# HD3SS460-PORT_1.net
KiCad netlist of a schematic drawn in Altium Designer
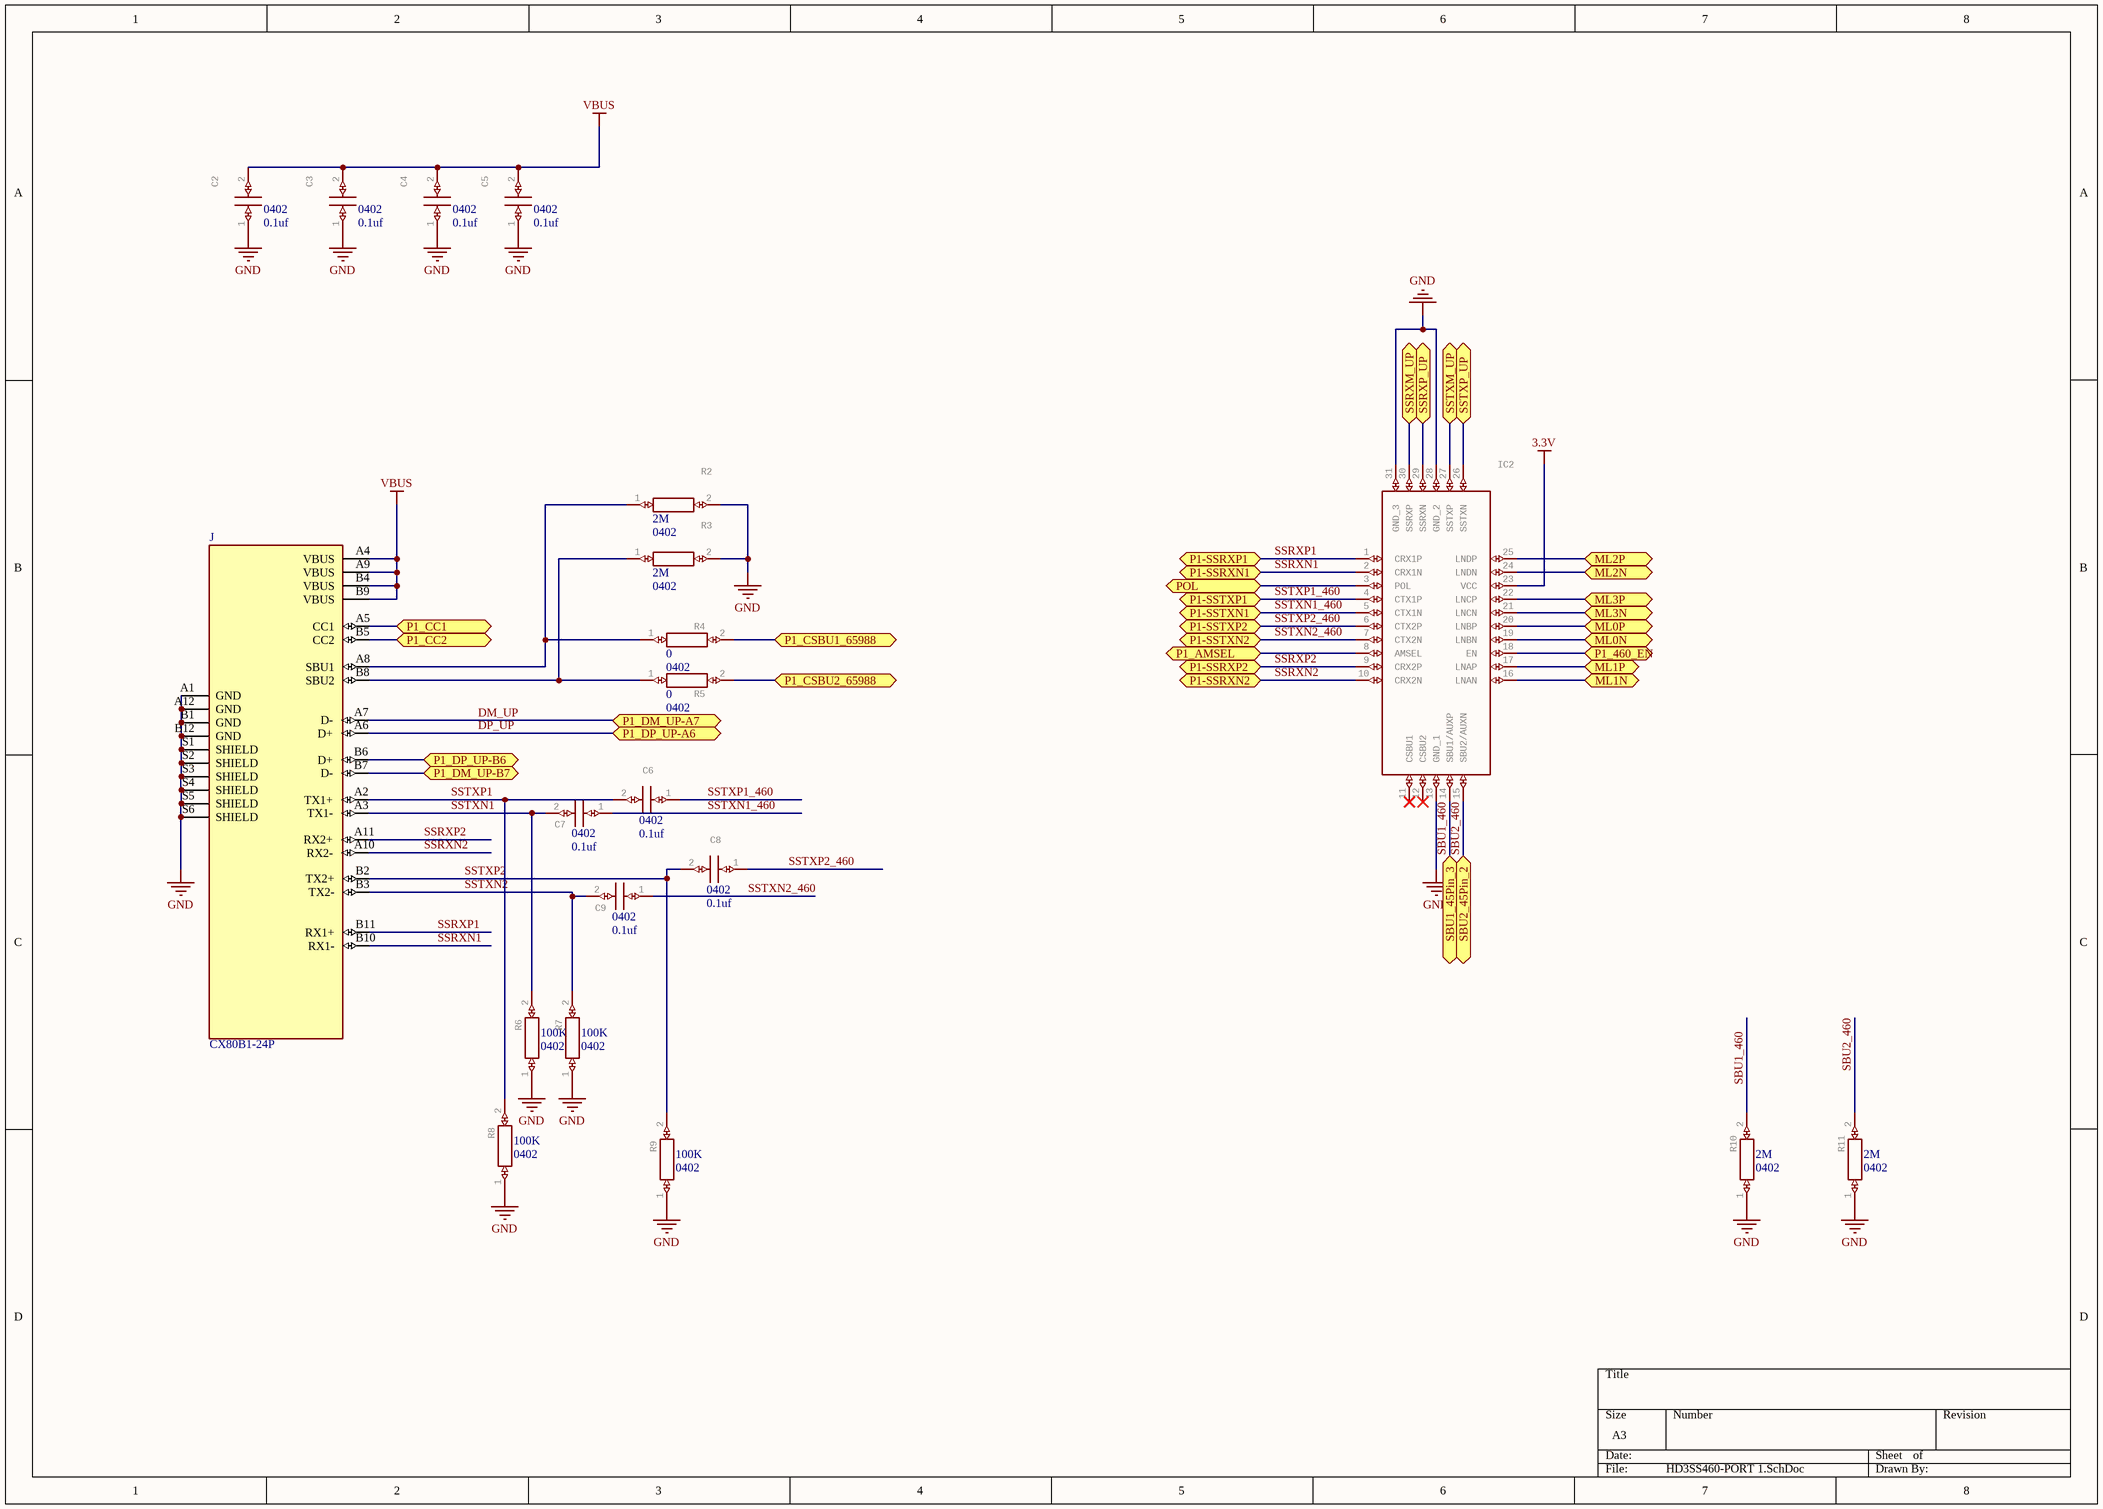
[diagram p0: HD3SS460-PORT 1.SchDoc]

(export (version "E")
  (design (tool "Eeschema 10.0.6"))
  (components
    (comp (ref "C2")
      (value "0.1uf")
      (footprint "CAPC1005X56N")
      (fields
        (field (name "MANUFACTURER_PART_NUMBER") "04025C104KAT2A")
        (field (name "MOUSER_PART_NUMBER") "581-04025C104KAT2A")
        (field (name "PACKAGE") "0402")
        (field (name "Comment") "Multilayer Ceramic Capacitors MLCC - SMD/SMT 50V .1uF X7R 0402 10% Tol   Source:  Datasheet")
      )
      (libsource (lib "C0402-GP") (part "04025C104KAT2A"))
    )
    (comp (ref "C3")
      (value "0.1uf")
      (footprint "CAPC1005X56N")
      (fields
        (field (name "MANUFACTURER_PART_NUMBER") "04025C104KAT2A")
        (field (name "MOUSER_PART_NUMBER") "581-04025C104KAT2A")
        (field (name "PACKAGE") "0402")
        (field (name "Comment") "Multilayer Ceramic Capacitors MLCC - SMD/SMT 50V .1uF X7R 0402 10% Tol   Source:  Datasheet")
      )
      (libsource (lib "C0402-GP") (part "04025C104KAT2A"))
    )
    (comp (ref "C4")
      (value "0.1uf")
      (footprint "CAPC1005X56N")
      (fields
        (field (name "MANUFACTURER_PART_NUMBER") "04025C104KAT2A")
        (field (name "MOUSER_PART_NUMBER") "581-04025C104KAT2A")
        (field (name "PACKAGE") "0402")
        (field (name "Comment") "Multilayer Ceramic Capacitors MLCC - SMD/SMT 50V .1uF X7R 0402 10% Tol   Source:  Datasheet")
      )
      (libsource (lib "C0402-GP") (part "04025C104KAT2A"))
    )
    (comp (ref "C5")
      (value "0.1uf")
      (footprint "CAPC1005X56N")
      (fields
        (field (name "MANUFACTURER_PART_NUMBER") "04025C104KAT2A")
        (field (name "MOUSER_PART_NUMBER") "581-04025C104KAT2A")
        (field (name "PACKAGE") "0402")
        (field (name "Comment") "Multilayer Ceramic Capacitors MLCC - SMD/SMT 50V .1uF X7R 0402 10% Tol   Source:  Datasheet")
      )
      (libsource (lib "C0402-GP") (part "04025C104KAT2A"))
    )
    (comp (ref "C6")
      (value "0.1uf")
      (footprint "CAPC1005X56N")
      (fields
        (field (name "MANUFACTURER_PART_NUMBER") "04025C104KAT2A")
        (field (name "MOUSER_PART_NUMBER") "581-04025C104KAT2A")
        (field (name "PACKAGE") "0402")
        (field (name "Comment") "Multilayer Ceramic Capacitors MLCC - SMD/SMT 50V .1uF X7R 0402 10% Tol   Source:  Datasheet")
      )
      (libsource (lib "C0402-GP") (part "04025C104KAT2A"))
    )
    (comp (ref "C7")
      (value "0.1uf")
      (footprint "CAPC1005X56N")
      (fields
        (field (name "MANUFACTURER_PART_NUMBER") "04025C104KAT2A")
        (field (name "MOUSER_PART_NUMBER") "581-04025C104KAT2A")
        (field (name "PACKAGE") "0402")
        (field (name "Comment") "Multilayer Ceramic Capacitors MLCC - SMD/SMT 50V .1uF X7R 0402 10% Tol   Source:  Datasheet")
      )
      (libsource (lib "C0402-GP") (part "04025C104KAT2A"))
    )
    (comp (ref "C8")
      (value "0.1uf")
      (footprint "CAPC1005X56N")
      (fields
        (field (name "MANUFACTURER_PART_NUMBER") "04025C104KAT2A")
        (field (name "MOUSER_PART_NUMBER") "581-04025C104KAT2A")
        (field (name "PACKAGE") "0402")
        (field (name "Comment") "Multilayer Ceramic Capacitors MLCC - SMD/SMT 50V .1uF X7R 0402 10% Tol   Source:  Datasheet")
      )
      (libsource (lib "C0402-GP") (part "04025C104KAT2A"))
    )
    (comp (ref "C9")
      (value "0.1uf")
      (footprint "CAPC1005X56N")
      (fields
        (field (name "MANUFACTURER_PART_NUMBER") "04025C104KAT2A")
        (field (name "MOUSER_PART_NUMBER") "581-04025C104KAT2A")
        (field (name "PACKAGE") "0402")
        (field (name "Comment") "Multilayer Ceramic Capacitors MLCC - SMD/SMT 50V .1uF X7R 0402 10% Tol   Source:  Datasheet")
      )
      (libsource (lib "C0402-GP") (part "04025C104KAT2A"))
    )
    (comp (ref "IC2")
      (value "USB Type-C Alternate Mode 4x6 Differential Switch   Source:  Datasheet")
      (footprint "QFN40P250X450X80-31N")
      (fields
        (field (name "MANUFACTURER_PART_NUMBER") "HD3SS460RNHR")
        (field (name "MOUSER_PART_NUMBER") "595-HD3SS460RNHR")
      )
      (libsource (lib "HD3SS460RNHR") (part "HD3SS460RNHR"))
    )
    (comp (ref "J")
      (value "CX80B1-24P")
      (footprint "HIROSE_CX80B1-24P")
      (fields
        (field (name "DIGI-KEY_PART_NUMBER") "26-CX80B1-24PCT-ND")
        (field (name "MF") "Hirose Electric Co Ltd")
      )
      (libsource (lib "CX80B1-24P") (part "CX80B1-24P"))
    )
    (comp (ref "R2")
      (value "2M")
      (footprint "RESC1005X40N")
      (fields
        (field (name "MANUFACTURER_PART_NUMBER") "RC0402FR-071KL")
        (field (name "MOUSER_PART_NUMBER") "603-RC0402FR-071KL")
        (field (name "PACKAGE") "0402")
        (field (name "Comment") "GENERAL PURPOSE CHIP RESISTORS   Source:  Datasheet")
      )
      (libsource (lib "R0402-GP") (part "RC0402FR-071KL"))
    )
    (comp (ref "R3")
      (value "2M")
      (footprint "RESC1005X40N")
      (fields
        (field (name "MANUFACTURER_PART_NUMBER") "RC0402FR-071KL")
        (field (name "MOUSER_PART_NUMBER") "603-RC0402FR-071KL")
        (field (name "PACKAGE") "0402")
        (field (name "Comment") "GENERAL PURPOSE CHIP RESISTORS   Source:  Datasheet")
      )
      (libsource (lib "R0402-GP") (part "RC0402FR-071KL"))
    )
    (comp (ref "R4")
      (value "0")
      (footprint "RESC1005X40N")
      (fields
        (field (name "MANUFACTURER_PART_NUMBER") "RC0402FR-071KL")
        (field (name "MOUSER_PART_NUMBER") "603-RC0402FR-071KL")
        (field (name "PACKAGE") "0402")
        (field (name "Comment") "GENERAL PURPOSE CHIP RESISTORS   Source:  Datasheet")
      )
      (libsource (lib "R0402-GP") (part "RC0402FR-071KL"))
    )
    (comp (ref "R5")
      (value "0")
      (footprint "RESC1005X40N")
      (fields
        (field (name "MANUFACTURER_PART_NUMBER") "RC0402FR-071KL")
        (field (name "MOUSER_PART_NUMBER") "603-RC0402FR-071KL")
        (field (name "PACKAGE") "0402")
        (field (name "Comment") "GENERAL PURPOSE CHIP RESISTORS   Source:  Datasheet")
      )
      (libsource (lib "R0402-GP") (part "RC0402FR-071KL"))
    )
    (comp (ref "R6")
      (value "100K")
      (footprint "RESC1005X40N")
      (fields
        (field (name "MANUFACTURER_PART_NUMBER") "RC0402FR-071KL")
        (field (name "MOUSER_PART_NUMBER") "603-RC0402FR-071KL")
        (field (name "PACKAGE") "0402")
        (field (name "Comment") "GENERAL PURPOSE CHIP RESISTORS   Source:  Datasheet")
      )
      (libsource (lib "R0402-GP") (part "RC0402FR-071KL"))
    )
    (comp (ref "R7")
      (value "100K")
      (footprint "RESC1005X40N")
      (fields
        (field (name "MANUFACTURER_PART_NUMBER") "RC0402FR-071KL")
        (field (name "MOUSER_PART_NUMBER") "603-RC0402FR-071KL")
        (field (name "PACKAGE") "0402")
        (field (name "Comment") "GENERAL PURPOSE CHIP RESISTORS   Source:  Datasheet")
      )
      (libsource (lib "R0402-GP") (part "RC0402FR-071KL"))
    )
    (comp (ref "R8")
      (value "100K")
      (footprint "RESC1005X40N")
      (fields
        (field (name "MANUFACTURER_PART_NUMBER") "RC0402FR-071KL")
        (field (name "MOUSER_PART_NUMBER") "603-RC0402FR-071KL")
        (field (name "PACKAGE") "0402")
        (field (name "Comment") "GENERAL PURPOSE CHIP RESISTORS   Source:  Datasheet")
      )
      (libsource (lib "R0402-GP") (part "RC0402FR-071KL"))
    )
    (comp (ref "R9")
      (value "100K")
      (footprint "RESC1005X40N")
      (fields
        (field (name "MANUFACTURER_PART_NUMBER") "RC0402FR-071KL")
        (field (name "MOUSER_PART_NUMBER") "603-RC0402FR-071KL")
        (field (name "PACKAGE") "0402")
        (field (name "Comment") "GENERAL PURPOSE CHIP RESISTORS   Source:  Datasheet")
      )
      (libsource (lib "R0402-GP") (part "RC0402FR-071KL"))
    )
    (comp (ref "R10")
      (value "2M")
      (footprint "RESC1005X40N")
      (fields
        (field (name "MANUFACTURER_PART_NUMBER") "RC0402FR-071KL")
        (field (name "MOUSER_PART_NUMBER") "603-RC0402FR-071KL")
        (field (name "PACKAGE") "0402")
        (field (name "Comment") "GENERAL PURPOSE CHIP RESISTORS   Source:  Datasheet")
      )
      (libsource (lib "R0402-GP") (part "RC0402FR-071KL"))
    )
    (comp (ref "R11")
      (value "2M")
      (footprint "RESC1005X40N")
      (fields
        (field (name "MANUFACTURER_PART_NUMBER") "RC0402FR-071KL")
        (field (name "MOUSER_PART_NUMBER") "603-RC0402FR-071KL")
        (field (name "PACKAGE") "0402")
        (field (name "Comment") "GENERAL PURPOSE CHIP RESISTORS   Source:  Datasheet")
      )
      (libsource (lib "R0402-GP") (part "RC0402FR-071KL"))
    )
  )
  (nets
    (net (code "2") (name "/DP_UP") (class "Default")
      (node (ref "J") (pin "A6") (pinfunction "D+_A6") (pintype "bidirectional"))
    )
    (net (code "3") (name "/ML0N") (class "Default")
      (node (ref "IC2") (pin "19") (pinfunction "LNBN_19") (pintype "bidirectional"))
    )
    (net (code "4") (name "/ML0P") (class "Default")
      (node (ref "IC2") (pin "20") (pinfunction "LNBP_20") (pintype "bidirectional"))
    )
    (net (code "5") (name "/ML1N") (class "Default")
      (node (ref "IC2") (pin "16") (pinfunction "LNAN_16") (pintype "bidirectional"))
    )
    (net (code "6") (name "/ML1P") (class "Default")
      (node (ref "IC2") (pin "17") (pinfunction "LNAP_17") (pintype "bidirectional"))
    )
    (net (code "7") (name "/ML2N") (class "Default")
      (node (ref "IC2") (pin "24") (pinfunction "LNDN_24") (pintype "bidirectional"))
    )
    (net (code "8") (name "/ML2P") (class "Default")
      (node (ref "IC2") (pin "25") (pinfunction "LNDP_25") (pintype "bidirectional"))
    )
    (net (code "9") (name "/ML3N") (class "Default")
      (node (ref "IC2") (pin "21") (pinfunction "LNCN_21") (pintype "bidirectional"))
    )
    (net (code "10") (name "/ML3P") (class "Default")
      (node (ref "IC2") (pin "22") (pinfunction "LNCP_22") (pintype "bidirectional"))
    )
    (net (code "11") (name "/P1_460_EN") (class "Default")
      (node (ref "IC2") (pin "18") (pinfunction "EN_18") (pintype "bidirectional"))
    )
    (net (code "12") (name "/P1_AMSEL") (class "Default")
      (node (ref "IC2") (pin "8") (pinfunction "AMSEL_8") (pintype "bidirectional"))
    )
    (net (code "13") (name "/P1_CC1") (class "Default")
      (node (ref "J") (pin "A5") (pinfunction "CC1_A5") (pintype "bidirectional"))
    )
    (net (code "14") (name "/P1_CC2") (class "Default")
      (node (ref "J") (pin "B5") (pinfunction "CC2_B5") (pintype "bidirectional"))
    )
    (net (code "15") (name "/P1_CSBU1_65988") (class "Default")
      (node (ref "R4") (pin "2") (pinfunction "2_2") (pintype "bidirectional"))
    )
    (net (code "16") (name "/P1_CSBU2_65988") (class "Default")
      (node (ref "R5") (pin "2") (pinfunction "2_2") (pintype "bidirectional"))
    )
    (net (code "18") (name "/P1_DM_UP-B7") (class "Default")
      (node (ref "J") (pin "B7") (pinfunction "D-_B7") (pintype "bidirectional"))
    )
    (net (code "19") (name "/P1_DP_UP-B6") (class "Default")
      (node (ref "J") (pin "B6") (pinfunction "D+_B6") (pintype "bidirectional"))
    )
    (net (code "20") (name "/POL") (class "Default")
      (node (ref "IC2") (pin "3") (pinfunction "POL_3") (pintype "bidirectional"))
    )
    (net (code "21") (name "/SBU1_460") (class "Default")
      (node (ref "IC2") (pin "14") (pinfunction "SBU1/AUXP_14") (pintype "bidirectional"))
      (node (ref "R10") (pin "2") (pinfunction "2_2") (pintype "bidirectional"))
    )
    (net (code "22") (name "/SBU2_460") (class "Default")
      (node (ref "IC2") (pin "15") (pinfunction "SBU2/AUXN_15") (pintype "bidirectional"))
      (node (ref "R11") (pin "2") (pinfunction "2_2") (pintype "bidirectional"))
    )
    (net (code "23") (name "/SSRXM_UP") (class "Default")
      (node (ref "IC2") (pin "30") (pinfunction "SSRXP_30") (pintype "bidirectional"))
    )
    (net (code "24") (name "/SSRXN1") (class "Default")
      (node (ref "IC2") (pin "2") (pinfunction "CRX1N_2") (pintype "bidirectional"))
      (node (ref "J") (pin "B10") (pinfunction "RX1-_B10") (pintype "bidirectional"))
    )
    (net (code "25") (name "/SSRXN2") (class "Default")
      (node (ref "IC2") (pin "10") (pinfunction "CRX2N_10") (pintype "bidirectional"))
      (node (ref "J") (pin "A10") (pinfunction "RX2-_A10") (pintype "bidirectional"))
    )
    (net (code "26") (name "/SSRXP1") (class "Default")
      (node (ref "IC2") (pin "1") (pinfunction "CRX1P_1") (pintype "bidirectional"))
      (node (ref "J") (pin "B11") (pinfunction "RX1+_B11") (pintype "bidirectional"))
    )
    (net (code "27") (name "/SSRXP2") (class "Default")
      (node (ref "IC2") (pin "9") (pinfunction "CRX2P_9") (pintype "bidirectional"))
      (node (ref "J") (pin "A11") (pinfunction "RX2+_A11") (pintype "bidirectional"))
    )
    (net (code "28") (name "/SSRXP_UP") (class "Default")
      (node (ref "IC2") (pin "29") (pinfunction "SSRXN_29") (pintype "bidirectional"))
    )
    (net (code "29") (name "/SSTXM_UP") (class "Default")
      (node (ref "IC2") (pin "27") (pinfunction "SSTXP_27") (pintype "bidirectional"))
    )
    (net (code "30") (name "/SSTXN1") (class "Default")
      (node (ref "C7") (pin "2") (pinfunction "2_2") (pintype "bidirectional"))
      (node (ref "J") (pin "A3") (pinfunction "TX1-_A3") (pintype "bidirectional"))
      (node (ref "R6") (pin "2") (pinfunction "2_2") (pintype "bidirectional"))
    )
    (net (code "31") (name "/SSTXN1_460") (class "Default")
      (node (ref "C7") (pin "1") (pinfunction "1_1") (pintype "bidirectional"))
      (node (ref "IC2") (pin "5") (pinfunction "CTX1N_5") (pintype "bidirectional"))
    )
    (net (code "32") (name "/SSTXN2") (class "Default")
      (node (ref "C9") (pin "2") (pinfunction "2_2") (pintype "bidirectional"))
      (node (ref "J") (pin "B3") (pinfunction "TX2-_B3") (pintype "bidirectional"))
      (node (ref "R7") (pin "2") (pinfunction "2_2") (pintype "bidirectional"))
    )
    (net (code "33") (name "/SSTXN2_460") (class "Default")
      (node (ref "C9") (pin "1") (pinfunction "1_1") (pintype "bidirectional"))
      (node (ref "IC2") (pin "7") (pinfunction "CTX2N_7") (pintype "bidirectional"))
    )
    (net (code "34") (name "/SSTXP1") (class "Default")
      (node (ref "C6") (pin "2") (pinfunction "2_2") (pintype "bidirectional"))
      (node (ref "J") (pin "A2") (pinfunction "TX1+_A2") (pintype "bidirectional"))
      (node (ref "R8") (pin "2") (pinfunction "2_2") (pintype "bidirectional"))
    )
    (net (code "35") (name "/SSTXP1_460") (class "Default")
      (node (ref "C6") (pin "1") (pinfunction "1_1") (pintype "bidirectional"))
      (node (ref "IC2") (pin "4") (pinfunction "CTX1P_4") (pintype "bidirectional"))
    )
    (net (code "36") (name "/SSTXP2") (class "Default")
      (node (ref "C8") (pin "2") (pinfunction "2_2") (pintype "bidirectional"))
      (node (ref "J") (pin "B2") (pinfunction "TX2+_B2") (pintype "bidirectional"))
      (node (ref "R9") (pin "2") (pinfunction "2_2") (pintype "bidirectional"))
    )
    (net (code "37") (name "/SSTXP2_460") (class "Default")
      (node (ref "C8") (pin "1") (pinfunction "1_1") (pintype "bidirectional"))
      (node (ref "IC2") (pin "6") (pinfunction "CTX2P_6") (pintype "bidirectional"))
    )
    (net (code "38") (name "/SSTXP_UP") (class "Default")
      (node (ref "IC2") (pin "26") (pinfunction "SSTXN_26") (pintype "bidirectional"))
    )
    (net (code "39") (name "3.3V") (class "Default")
      (node (ref "IC2") (pin "23") (pinfunction "VCC_23") (pintype "bidirectional"))
    )
    (net (code "40") (name "GND") (class "Default")
      (node (ref "C2") (pin "1") (pinfunction "1_1") (pintype "bidirectional"))
      (node (ref "C3") (pin "1") (pinfunction "1_1") (pintype "bidirectional"))
      (node (ref "C4") (pin "1") (pinfunction "1_1") (pintype "bidirectional"))
      (node (ref "C5") (pin "1") (pinfunction "1_1") (pintype "bidirectional"))
      (node (ref "IC2") (pin "13") (pinfunction "GND_1_13") (pintype "bidirectional"))
      (node (ref "IC2") (pin "28") (pinfunction "GND_2_28") (pintype "bidirectional"))
      (node (ref "IC2") (pin "31") (pinfunction "GND_3_31") (pintype "bidirectional"))
      (node (ref "J") (pin "A1") (pinfunction "GND_A1") (pintype "power_in"))
      (node (ref "J") (pin "A12") (pinfunction "GND_A12") (pintype "power_in"))
      (node (ref "J") (pin "B1") (pinfunction "GND_B1") (pintype "power_in"))
      (node (ref "J") (pin "B12") (pinfunction "GND_B12") (pintype "power_in"))
      (node (ref "J") (pin "S1") (pinfunction "SHIELD_S1") (pintype "power_in"))
      (node (ref "J") (pin "S2") (pinfunction "SHIELD_S2") (pintype "power_in"))
      (node (ref "J") (pin "S3") (pinfunction "SHIELD_S3") (pintype "power_in"))
      (node (ref "J") (pin "S4") (pinfunction "SHIELD_S4") (pintype "power_in"))
      (node (ref "J") (pin "S5") (pinfunction "SHIELD_S5") (pintype "power_in"))
      (node (ref "J") (pin "S6") (pinfunction "SHIELD_S6") (pintype "power_in"))
      (node (ref "R10") (pin "1") (pinfunction "1_1") (pintype "bidirectional"))
      (node (ref "R11") (pin "1") (pinfunction "1_1") (pintype "bidirectional"))
      (node (ref "R2") (pin "2") (pinfunction "2_2") (pintype "bidirectional"))
      (node (ref "R3") (pin "2") (pinfunction "2_2") (pintype "bidirectional"))
      (node (ref "R6") (pin "1") (pinfunction "1_1") (pintype "bidirectional"))
      (node (ref "R7") (pin "1") (pinfunction "1_1") (pintype "bidirectional"))
      (node (ref "R8") (pin "1") (pinfunction "1_1") (pintype "bidirectional"))
      (node (ref "R9") (pin "1") (pinfunction "1_1") (pintype "bidirectional"))
    )
    (net (code "41") (name "Net-(J-SBU1)") (class "Default")
      (node (ref "J") (pin "A8") (pinfunction "SBU1_A8") (pintype "bidirectional"))
      (node (ref "R2") (pin "1") (pinfunction "1_1") (pintype "bidirectional"))
      (node (ref "R4") (pin "1") (pinfunction "1_1") (pintype "bidirectional"))
    )
    (net (code "42") (name "Net-(J-SBU2)") (class "Default")
      (node (ref "J") (pin "B8") (pinfunction "SBU2_B8") (pintype "bidirectional"))
      (node (ref "R3") (pin "1") (pinfunction "1_1") (pintype "bidirectional"))
      (node (ref "R5") (pin "1") (pinfunction "1_1") (pintype "bidirectional"))
    )
    (net (code "43") (name "VBUS") (class "Default")
      (node (ref "C2") (pin "2") (pinfunction "2_2") (pintype "bidirectional"))
      (node (ref "C3") (pin "2") (pinfunction "2_2") (pintype "bidirectional"))
      (node (ref "C4") (pin "2") (pinfunction "2_2") (pintype "bidirectional"))
      (node (ref "C5") (pin "2") (pinfunction "2_2") (pintype "bidirectional"))
      (node (ref "J") (pin "A4") (pinfunction "VBUS_A4") (pintype "power_in"))
      (node (ref "J") (pin "A9") (pinfunction "VBUS_A9") (pintype "power_in"))
      (node (ref "J") (pin "B4") (pinfunction "VBUS_B4") (pintype "power_in"))
      (node (ref "J") (pin "B9") (pinfunction "VBUS_B9") (pintype "power_in"))
    )
    (net (code "44") (name "unconnected-(IC2-CSBU1-Pad11)") (class "Default")
      (node (ref "IC2") (pin "11") (pinfunction "CSBU1_11") (pintype "bidirectional+no_connect"))
    )
    (net (code "45") (name "unconnected-(IC2-CSBU2-Pad12)") (class "Default")
      (node (ref "IC2") (pin "12") (pinfunction "CSBU2_12") (pintype "bidirectional+no_connect"))
    )
    (net (code "46") (name "unconnected-(J-D--PadA7)") (class "Default")
      (node (ref "J") (pin "A7") (pinfunction "D-_A7") (pintype "bidirectional"))
    )
  )
)
